# Sheet1.net
KiCad netlist of a schematic drawn in Altium Designer
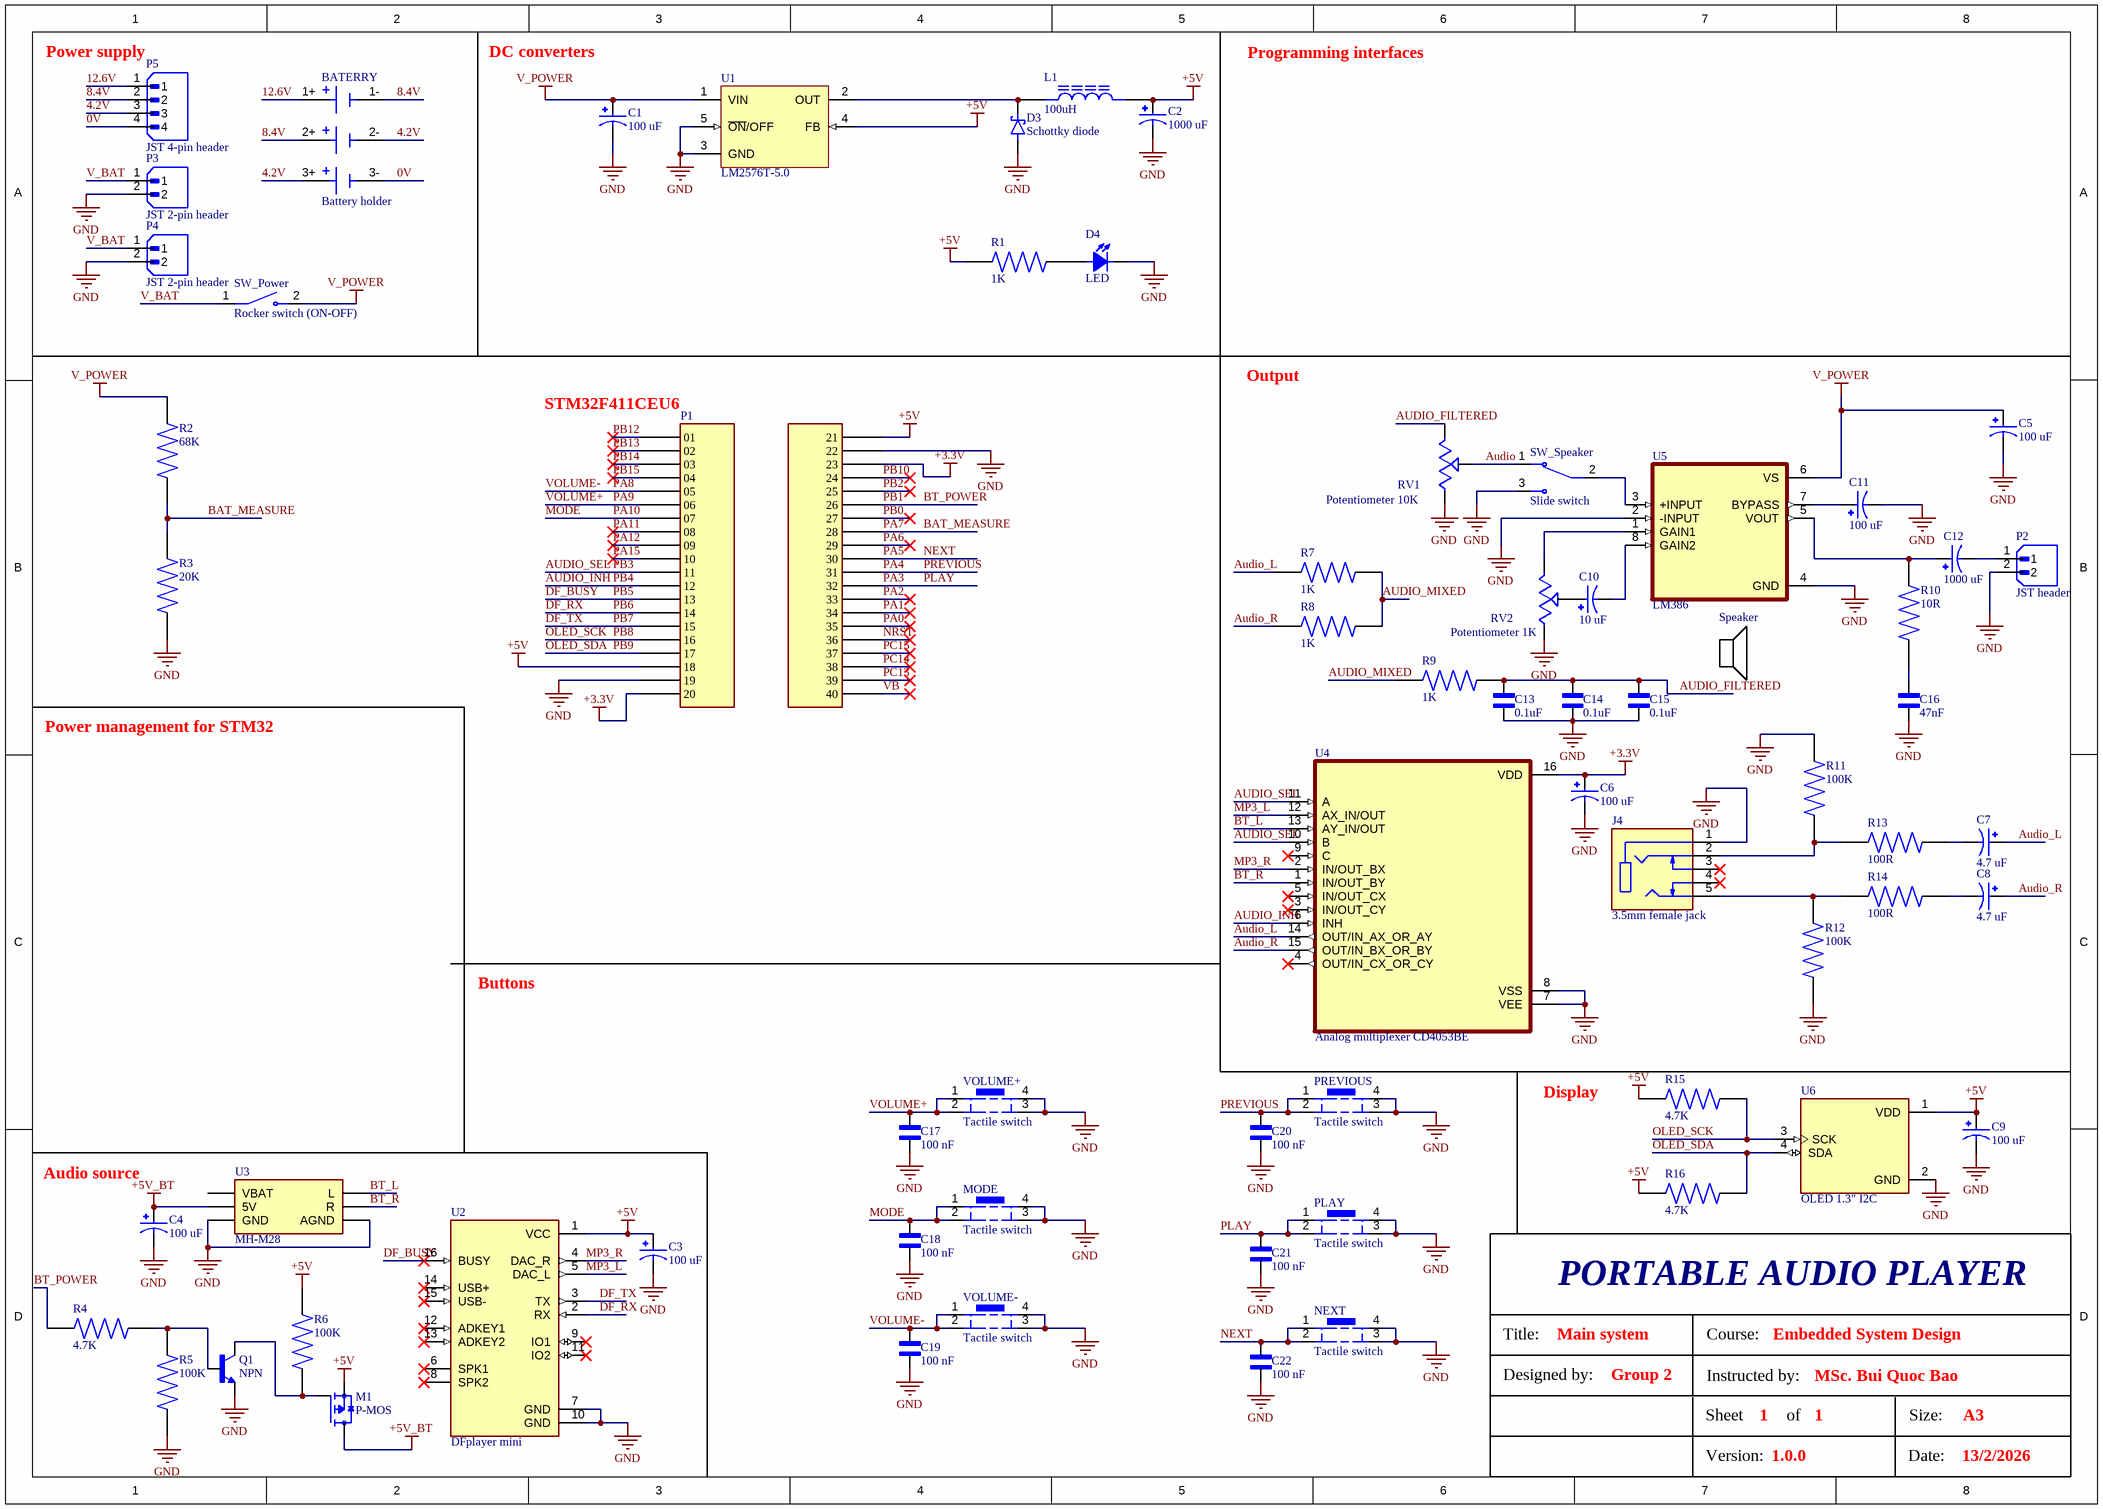
[diagram p0: Sheet1.SchDoc]

(export (version "E")
  (design (tool "Eeschema 10.0.6"))
  (components
    (comp (ref "BATERRY")
      (value "Battery holder")
      (footprint "BAT_BK-18650-PC6")
      (libsource (lib "Schlib1") (part "Battery holder"))
    )
    (comp (ref "C1")
      (value "100 uF")
      (footprint "CAPPRD250W50D630H1120")
      (libsource (lib "Schlib1") (part "100 uF"))
    )
    (comp (ref "C2")
      (value "1000 uF")
      (footprint "CAPPRD500W60D1000H2500")
      (libsource (lib "Schlib1") (part "1000 uF"))
    )
    (comp (ref "C3")
      (value "100 uF")
      (footprint "CAPPRD250W50D630H1120")
      (libsource (lib "Schlib1") (part "100 uF"))
    )
    (comp (ref "C4")
      (value "100 uF")
      (footprint "CAPPRD250W50D630H1120")
      (libsource (lib "Schlib1") (part "100 uF"))
    )
    (comp (ref "C5")
      (value "100 uF")
      (footprint "CAPPRD250W50D630H1120")
      (libsource (lib "Schlib1") (part "100 uF"))
    )
    (comp (ref "C6")
      (value "100 uF")
      (footprint "CAPPRD250W50D630H1120")
      (libsource (lib "Schlib1") (part "100 uF"))
    )
    (comp (ref "C7")
      (value "4.7 uF")
      (footprint "CAPPRD200W50D500H1100")
      (libsource (lib "Schlib1") (part "4.7 uF"))
    )
    (comp (ref "C8")
      (value "4.7 uF")
      (footprint "CAPPRD200W50D500H1100")
      (libsource (lib "Schlib1") (part "4.7 uF"))
    )
    (comp (ref "C9")
      (value "100 uF")
      (footprint "CAPPRD250W50D630H1120")
      (libsource (lib "Schlib1") (part "100 uF"))
    )
    (comp (ref "C10")
      (value "10 uF")
      (footprint "CAPPRD200W50D500H1100")
      (libsource (lib "Schlib1") (part "10 uF"))
    )
    (comp (ref "C11")
      (value "100 uF")
      (footprint "CAPPRD250W50D630H1120")
      (libsource (lib "") (part "100 uF_1"))
    )
    (comp (ref "C12")
      (value "1000 uF")
      (footprint "CAPPRD500W60D1000H2500")
      (libsource (lib "") (part "1000 uF_1"))
    )
    (comp (ref "C13")
      (value "0.1uF")
      (footprint "CAPRR254W54L381T254H466")
      (libsource (lib "Schlib1") (part "0.1uF"))
    )
    (comp (ref "C14")
      (value "0.1uF")
      (footprint "CAPRR254W54L381T254H466")
      (libsource (lib "Schlib1") (part "0.1uF"))
    )
    (comp (ref "C15")
      (value "0.1uF")
      (footprint "CAPRR254W54L381T254H466")
      (libsource (lib "Schlib1") (part "0.1uF"))
    )
    (comp (ref "C16")
      (value "47nF")
      (footprint "CAPRR254W50L508T317H508")
      (libsource (lib "Schlib1") (part "47nF"))
    )
    (comp (ref "C17")
      (value "100 nF")
      (footprint "CAPRR254W54L381T254H466")
      (libsource (lib "Schlib1") (part "100 nF"))
    )
    (comp (ref "C18")
      (value "100 nF")
      (footprint "CAPRR254W54L381T254H466")
      (libsource (lib "Schlib1") (part "100 nF"))
    )
    (comp (ref "C19")
      (value "100 nF")
      (footprint "CAPRR254W54L381T254H466")
      (libsource (lib "Schlib1") (part "100 nF"))
    )
    (comp (ref "C20")
      (value "100 nF")
      (footprint "CAPRR254W54L381T254H466")
      (libsource (lib "Schlib1") (part "100 nF"))
    )
    (comp (ref "C21")
      (value "100 nF")
      (footprint "CAPRR254W54L381T254H466")
      (libsource (lib "Schlib1") (part "100 nF"))
    )
    (comp (ref "C22")
      (value "100 nF")
      (footprint "CAPRR254W54L381T254H466")
      (libsource (lib "Schlib1") (part "100 nF"))
    )
    (comp (ref "D3")
      (value "Schottky diode")
      (footprint "DIOAD1039W78L463D236")
      (libsource (lib "Schlib1") (part "Schottky diode"))
    )
    (comp (ref "D4") (value "LED") (footprint "LED-TH-2.54mm") (libsource (lib "Schlib1") (part "LED")))
    (comp (ref "J4")
      (value "3.5mm female jack")
      (footprint "CLIFF_FC68133")
      (libsource (lib "Schlib1") (part "3.5mm female jack"))
    )
    (comp (ref "L1")
      (value "100uH")
      (footprint "IND_RLB9012-101KL")
      (libsource (lib "Schlib1") (part "100uH"))
    )
    (comp (ref "M1")
      (value "P-MOS")
      (footprint "TO254P1067X483X2286-3")
      (libsource (lib "Schlib1") (part "P-MOS"))
    )
    (comp (ref "MODE")
      (value "Tactile switch")
      (footprint "Tactice-Switch-TH-12x12")
      (libsource (lib "Schlib1") (part "Tactile switch"))
    )
    (comp (ref "NEXT")
      (value "Tactile switch")
      (footprint "Tactice-Switch-TH-12x12")
      (libsource (lib "Schlib1") (part "Tactile switch"))
    )
    (comp (ref "P1")
      (value "2x20 female header for mounting Blackpill board")
      (footprint "Blackpill board mounting headers")
      (libsource (lib "Schlib1") (part "2x20 female header for mounting Blackpill board"))
    )
    (comp (ref "P2")
      (value "JST header")
      (footprint "JST_B2B-XH-A")
      (libsource (lib "Schlib1") (part "JST header"))
    )
    (comp (ref "P3")
      (value "JST 2-pin header")
      (footprint "JST_B2B-XH-A")
      (libsource (lib "Schlib1") (part "JST 2-pin header"))
    )
    (comp (ref "P4")
      (value "JST 2-pin header")
      (footprint "JST_B2B-XH-A")
      (libsource (lib "Schlib1") (part "JST 2-pin header"))
    )
    (comp (ref "P5")
      (value "JST 4-pin header")
      (footprint "JST_B4B-XH-A")
      (libsource (lib "Schlib1") (part "JST 4-pin header"))
    )
    (comp (ref "PLAY")
      (value "Tactile switch")
      (footprint "Tactice-Switch-TH-12x12")
      (libsource (lib "Schlib1") (part "Tactile switch"))
    )
    (comp (ref "PREVIOUS")
      (value "Tactile switch")
      (footprint "Tactice-Switch-TH-12x12")
      (libsource (lib "Schlib1") (part "Tactile switch"))
    )
    (comp (ref "Q1") (value "NPN") (footprint "TO92254P460H750-3") (libsource (lib "Schlib1") (part "NPN")))
    (comp (ref "R1") (value "1K") (footprint "RESAD1100W55L680D260") (libsource (lib "Schlib1") (part "1K")))
    (comp (ref "R2")
      (value "68K")
      (footprint "RESAD1100W55L680D260")
      (libsource (lib "Schlib1") (part "68K"))
    )
    (comp (ref "R3")
      (value "20K")
      (footprint "RESAD1100W55L680D260")
      (libsource (lib "Schlib1") (part "20K"))
    )
    (comp (ref "R4")
      (value "4.7K")
      (footprint "RESAD1100W55L680D260")
      (libsource (lib "Schlib1") (part "4.7K"))
    )
    (comp (ref "R5")
      (value "100K")
      (footprint "RESAD1100W55L680D260")
      (libsource (lib "Schlib1") (part "100K"))
    )
    (comp (ref "R6")
      (value "100K")
      (footprint "RESAD1100W55L680D260")
      (libsource (lib "Schlib1") (part "100K"))
    )
    (comp (ref "R7") (value "1K") (footprint "RESAD1100W55L680D260") (libsource (lib "Schlib1") (part "1K")))
    (comp (ref "R8") (value "1K") (footprint "RESAD1100W55L680D260") (libsource (lib "Schlib1") (part "1K")))
    (comp (ref "R9") (value "1K") (footprint "RESAD1100W55L680D260") (libsource (lib "Schlib1") (part "1K")))
    (comp (ref "R10")
      (value "10R")
      (footprint "RESAD1100W55L680D260")
      (libsource (lib "Schlib1") (part "10R"))
    )
    (comp (ref "R11")
      (value "100K")
      (footprint "RESAD1100W55L680D260")
      (libsource (lib "Schlib1") (part "100K"))
    )
    (comp (ref "R12")
      (value "100K")
      (footprint "RESAD1100W55L680D260")
      (libsource (lib "Schlib1") (part "100K"))
    )
    (comp (ref "R13")
      (value "100R")
      (footprint "RESAD1100W55L680D260")
      (libsource (lib "Schlib1") (part "100R"))
    )
    (comp (ref "R14")
      (value "100R")
      (footprint "RESAD1100W55L680D260")
      (libsource (lib "Schlib1") (part "100R"))
    )
    (comp (ref "R15")
      (value "4.7K")
      (footprint "RESAD1100W55L680D260")
      (libsource (lib "Schlib1") (part "4.7K"))
    )
    (comp (ref "R16")
      (value "4.7K")
      (footprint "RESAD1100W55L680D260")
      (libsource (lib "Schlib1") (part "4.7K"))
    )
    (comp (ref "RV1")
      (value "Potentiometer 10K")
      (footprint "TRIM_WH148-1A-2-18T-L20")
      (libsource (lib "Schlib1") (part "Potentiometer 10K"))
    )
    (comp (ref "RV2")
      (value "Potentiometer 1K")
      (footprint "TRIM_WH148-1A-2-18T-L20")
      (libsource (lib "Schlib1") (part "Potentiometer 1K"))
    )
    (comp (ref "Speaker")
      (value "Speaker")
      (footprint "50mm speaker")
      (libsource (lib "Schlib1") (part "Speaker"))
    )
    (comp (ref "SW_Power")
      (value "Rocker switch (ON-OFF)")
      (footprint "Rocker switch (ON-OFF)")
      (libsource (lib "Schlib1") (part "Rocker switch (ON-OFF)"))
    )
    (comp (ref "SW_Speaker")
      (value "Slide switch")
      (footprint "SW_SLW-1276864-4A-D")
      (libsource (lib "Schlib1") (part "Slide switch"))
    )
    (comp (ref "U1")
      (value "LM2576T-5.0")
      (footprint "KC0005A")
      (description "SIMPLE SWITCHER® 3A Step-Down Voltage Regulator, 5-pin TO-220")
      (fields (field (name "MANUFACTURER") "Texas Instruments"))
      (libsource (lib "Altium Content Vault") (part "PM-REG-LM2575HVT-12"))
    )
    (comp (ref "U2")
      (value "DFplayer mini")
      (footprint "MODULE_DFR0299")
      (libsource (lib "Schlib1") (part "DFplayer mini"))
    )
    (comp (ref "U3") (value "MH-M28") (footprint "MH-M28") (libsource (lib "Schlib1") (part "MH-M28")))
    (comp (ref "U4")
      (value "Analog multiplexer CD4053BE")
      (footprint "DIP_16")
      (libsource (lib "Schlib1") (part "Analog multiplexer CD4053BE"))
    )
    (comp (ref "U5") (value "LM386") (footprint "DIP_8") (libsource (lib "Schlib1") (part "LM386")))
    (comp (ref "U6")
      (value "OLED 1.3\" I2C")
      (footprint "LCD_OLED_128X64_1.3_I2C")
      (libsource (lib "Schlib1") (part "OLED 1.3{dblquote} I2C"))
    )
    (comp (ref "VOLUME+")
      (value "Tactile switch")
      (footprint "Tactice-Switch-TH-12x12")
      (libsource (lib "Schlib1") (part "Tactile switch"))
    )
    (comp (ref "VOLUME-")
      (value "Tactile switch")
      (footprint "Tactice-Switch-TH-12x12")
      (libsource (lib "Schlib1") (part "Tactile switch"))
    )
  )
  (nets
    (net (code "1") (name "+3.3V") (class "Default")
      (node (ref "C6") (pin "P") (pinfunction "P_P") (pintype "passive"))
      (node (ref "P1") (pin "20") (pinfunction "20_20") (pintype "passive"))
      (node (ref "P1") (pin "23") (pinfunction "23_23") (pintype "passive"))
      (node (ref "U4") (pin "16") (pinfunction "VDD_16") (pintype "power_in"))
    )
    (net (code "2") (name "+5V") (class "Default")
      (node (ref "C2") (pin "P") (pinfunction "P_P") (pintype "passive"))
      (node (ref "C3") (pin "P") (pinfunction "P_P") (pintype "passive"))
      (node (ref "C9") (pin "P") (pinfunction "P_P") (pintype "passive"))
      (node (ref "L1") (pin "2") (pinfunction "2_2") (pintype "passive"))
      (node (ref "M1") (pin "3") (pinfunction "S_3") (pintype "passive"))
      (node (ref "P1") (pin "18") (pinfunction "18_18") (pintype "passive"))
      (node (ref "P1") (pin "21") (pinfunction "21_21") (pintype "passive"))
      (node (ref "R1") (pin "1") (pinfunction "1_1") (pintype "passive"))
      (node (ref "R15") (pin "2") (pinfunction "2_2") (pintype "passive"))
      (node (ref "R16") (pin "1") (pinfunction "1_1") (pintype "passive"))
      (node (ref "R6") (pin "2") (pinfunction "2_2") (pintype "passive"))
      (node (ref "U1") (pin "4") (pinfunction "FB_4") (pintype "input"))
      (node (ref "U2") (pin "1") (pinfunction "VCC_1") (pintype "power_in"))
      (node (ref "U6") (pin "1") (pinfunction "VDD_1") (pintype "power_in"))
    )
    (net (code "3") (name "+5V_BT") (class "Default")
      (node (ref "C4") (pin "P") (pinfunction "P_P") (pintype "passive"))
      (node (ref "M1") (pin "2") (pinfunction "D_2") (pintype "passive"))
      (node (ref "U3") (pin "5V") (pinfunction "5V_5V") (pintype "passive"))
    )
    (net (code "4") (name "/0V") (class "Default")
      (node (ref "BATERRY") (pin "3-") (pinfunction "3-_3-") (pintype "passive"))
      (node (ref "P5") (pin "4") (pinfunction "4_4") (pintype "passive"))
    )
    (net (code "5") (name "/4.2V") (class "Default")
      (node (ref "BATERRY") (pin "2-") (pinfunction "2-_2-") (pintype "passive"))
      (node (ref "BATERRY") (pin "3+") (pinfunction "3+_3+") (pintype "passive"))
      (node (ref "P5") (pin "3") (pinfunction "3_3") (pintype "passive"))
    )
    (net (code "6") (name "/8.4V") (class "Default")
      (node (ref "BATERRY") (pin "1-") (pinfunction "1-_1-") (pintype "passive"))
      (node (ref "BATERRY") (pin "2+") (pinfunction "2+_2+") (pintype "passive"))
      (node (ref "P5") (pin "2") (pinfunction "2_2") (pintype "passive"))
    )
    (net (code "7") (name "/12.6V") (class "Default")
      (node (ref "BATERRY") (pin "1+") (pinfunction "1+_1+") (pintype "passive"))
      (node (ref "P5") (pin "1") (pinfunction "1_1") (pintype "passive"))
    )
    (net (code "8") (name "/AUDIO_FILTERED") (class "Default")
      (node (ref "C13") (pin "2") (pinfunction "2_2") (pintype "passive"))
      (node (ref "C14") (pin "2") (pinfunction "2_2") (pintype "passive"))
      (node (ref "C15") (pin "2") (pinfunction "2_2") (pintype "passive"))
      (node (ref "R9") (pin "2") (pinfunction "2_2") (pintype "passive"))
      (node (ref "RV1") (pin "1") (pinfunction "1_1") (pintype "passive"))
    )
    (net (code "9") (name "/AUDIO_INH") (class "Default")
      (node (ref "P1") (pin "12") (pinfunction "12_12") (pintype "passive"))
      (node (ref "U4") (pin "6") (pinfunction "INH_6") (pintype "input"))
    )
    (net (code "10") (name "/AUDIO_MIXED") (class "Default")
      (node (ref "R7") (pin "2") (pinfunction "2_2") (pintype "passive"))
      (node (ref "R8") (pin "2") (pinfunction "2_2") (pintype "passive"))
      (node (ref "R9") (pin "1") (pinfunction "1_1") (pintype "passive"))
    )
    (net (code "11") (name "/AUDIO_SEL") (class "Default")
      (node (ref "P1") (pin "11") (pinfunction "11_11") (pintype "passive"))
      (node (ref "U4") (pin "10") (pinfunction "B_10") (pintype "input"))
      (node (ref "U4") (pin "11") (pinfunction "A_11") (pintype "input"))
    )
    (net (code "12") (name "/Audio") (class "Default")
      (node (ref "RV1") (pin "2") (pinfunction "2_2") (pintype "passive"))
      (node (ref "SW_Speaker") (pin "1") (pinfunction "1_1") (pintype "passive"))
    )
    (net (code "13") (name "/Audio_L") (class "Default")
      (node (ref "C7") (pin "P") (pinfunction "P_P") (pintype "passive"))
      (node (ref "R7") (pin "1") (pinfunction "1_1") (pintype "passive"))
      (node (ref "U4") (pin "14") (pinfunction "OUT/IN_AX_OR_AY_14") (pintype "output"))
    )
    (net (code "14") (name "/Audio_R") (class "Default")
      (node (ref "C8") (pin "P") (pinfunction "P_P") (pintype "passive"))
      (node (ref "R8") (pin "1") (pinfunction "1_1") (pintype "passive"))
      (node (ref "U4") (pin "15") (pinfunction "OUT/IN_BX_OR_BY_15") (pintype "output"))
    )
    (net (code "15") (name "/BAT_MEASURE") (class "Default")
      (node (ref "P1") (pin "28") (pinfunction "28_28") (pintype "passive"))
      (node (ref "R2") (pin "1") (pinfunction "1_1") (pintype "passive"))
      (node (ref "R3") (pin "2") (pinfunction "2_2") (pintype "passive"))
    )
    (net (code "16") (name "/BT_L") (class "Default")
      (node (ref "U3") (pin "L") (pinfunction "L_L") (pintype "passive"))
      (node (ref "U4") (pin "13") (pinfunction "AY_IN/OUT_13") (pintype "input"))
    )
    (net (code "17") (name "/BT_POWER") (class "Default")
      (node (ref "P1") (pin "26") (pinfunction "26_26") (pintype "passive"))
      (node (ref "R4") (pin "1") (pinfunction "1_1") (pintype "passive"))
    )
    (net (code "18") (name "/BT_R") (class "Default")
      (node (ref "U3") (pin "R") (pinfunction "R_R") (pintype "passive"))
      (node (ref "U4") (pin "1") (pinfunction "IN/OUT_BY_1") (pintype "input"))
    )
    (net (code "19") (name "/DF_BUSY") (class "Default")
      (node (ref "P1") (pin "13") (pinfunction "13_13") (pintype "passive"))
      (node (ref "U2") (pin "16") (pinfunction "BUSY_16") (pintype "input"))
    )
    (net (code "20") (name "/DF_RX") (class "Default")
      (node (ref "P1") (pin "14") (pinfunction "14_14") (pintype "passive"))
      (node (ref "U2") (pin "2") (pinfunction "RX_2") (pintype "input"))
    )
    (net (code "21") (name "/DF_TX") (class "Default")
      (node (ref "P1") (pin "15") (pinfunction "15_15") (pintype "passive"))
      (node (ref "U2") (pin "3") (pinfunction "TX_3") (pintype "output"))
    )
    (net (code "22") (name "/MODE") (class "Default")
      (node (ref "C18") (pin "2") (pinfunction "2_2") (pintype "passive"))
      (node (ref "MODE") (pin "1") (pinfunction "1_1") (pintype "passive"))
      (node (ref "MODE") (pin "2") (pinfunction "2_2") (pintype "passive"))
      (node (ref "P1") (pin "7") (pinfunction "07_7") (pintype "passive"))
    )
    (net (code "23") (name "/MP3_L") (class "Default")
      (node (ref "U2") (pin "5") (pinfunction "DAC_L_5") (pintype "output"))
      (node (ref "U4") (pin "12") (pinfunction "AX_IN/OUT_12") (pintype "input"))
    )
    (net (code "24") (name "/MP3_R") (class "Default")
      (node (ref "U2") (pin "4") (pinfunction "DAC_R_4") (pintype "output"))
      (node (ref "U4") (pin "2") (pinfunction "IN/OUT_BX_2") (pintype "input"))
    )
    (net (code "25") (name "/NEXT") (class "Default")
      (node (ref "C22") (pin "2") (pinfunction "2_2") (pintype "passive"))
      (node (ref "NEXT") (pin "1") (pinfunction "1_1") (pintype "passive"))
      (node (ref "NEXT") (pin "2") (pinfunction "2_2") (pintype "passive"))
      (node (ref "P1") (pin "30") (pinfunction "30_30") (pintype "passive"))
    )
    (net (code "26") (name "/NRST") (class "Default")
      (node (ref "P1") (pin "36") (pinfunction "36_36") (pintype "passive+no_connect"))
    )
    (net (code "27") (name "/OLED_SCK") (class "Default")
      (node (ref "P1") (pin "16") (pinfunction "16_16") (pintype "passive"))
      (node (ref "R15") (pin "1") (pinfunction "1_1") (pintype "passive"))
      (node (ref "U6") (pin "3") (pinfunction "SCK_3") (pintype "input"))
    )
    (net (code "28") (name "/OLED_SDA") (class "Default")
      (node (ref "P1") (pin "17") (pinfunction "17_17") (pintype "passive"))
      (node (ref "R16") (pin "2") (pinfunction "2_2") (pintype "passive"))
      (node (ref "U6") (pin "4") (pinfunction "SDA_4") (pintype "bidirectional"))
    )
    (net (code "29") (name "/PA0") (class "Default")
      (node (ref "P1") (pin "35") (pinfunction "35_35") (pintype "passive+no_connect"))
    )
    (net (code "30") (name "/PA1") (class "Default")
      (node (ref "P1") (pin "34") (pinfunction "34_34") (pintype "passive+no_connect"))
    )
    (net (code "31") (name "/PA2") (class "Default")
      (node (ref "P1") (pin "33") (pinfunction "33_33") (pintype "passive+no_connect"))
    )
    (net (code "32") (name "/PA3") (class "Default")
      (node (ref "C21") (pin "2") (pinfunction "2_2") (pintype "passive"))
      (node (ref "P1") (pin "32") (pinfunction "32_32") (pintype "passive"))
      (node (ref "PLAY") (pin "1") (pinfunction "1_1") (pintype "passive"))
      (node (ref "PLAY") (pin "2") (pinfunction "2_2") (pintype "passive"))
    )
    (net (code "33") (name "/PA4") (class "Default")
      (node (ref "C20") (pin "2") (pinfunction "2_2") (pintype "passive"))
      (node (ref "P1") (pin "31") (pinfunction "31_31") (pintype "passive"))
      (node (ref "PREVIOUS") (pin "1") (pinfunction "1_1") (pintype "passive"))
      (node (ref "PREVIOUS") (pin "2") (pinfunction "2_2") (pintype "passive"))
    )
    (net (code "34") (name "/PA6") (class "Default")
      (node (ref "P1") (pin "29") (pinfunction "29_29") (pintype "passive+no_connect"))
    )
    (net (code "35") (name "/PA8") (class "Default")
      (node (ref "C19") (pin "2") (pinfunction "2_2") (pintype "passive"))
      (node (ref "P1") (pin "5") (pinfunction "05_5") (pintype "passive"))
      (node (ref "VOLUME-") (pin "1") (pinfunction "1_1") (pintype "passive"))
      (node (ref "VOLUME-") (pin "2") (pinfunction "2_2") (pintype "passive"))
    )
    (net (code "36") (name "/PA9") (class "Default")
      (node (ref "C17") (pin "2") (pinfunction "2_2") (pintype "passive"))
      (node (ref "P1") (pin "6") (pinfunction "06_6") (pintype "passive"))
      (node (ref "VOLUME+") (pin "1") (pinfunction "1_1") (pintype "passive"))
      (node (ref "VOLUME+") (pin "2") (pinfunction "2_2") (pintype "passive"))
    )
    (net (code "37") (name "/PA11") (class "Default")
      (node (ref "P1") (pin "8") (pinfunction "08_8") (pintype "passive+no_connect"))
    )
    (net (code "38") (name "/PA12") (class "Default")
      (node (ref "P1") (pin "9") (pinfunction "09_9") (pintype "passive+no_connect"))
    )
    (net (code "39") (name "/PA15") (class "Default")
      (node (ref "P1") (pin "10") (pinfunction "10_10") (pintype "passive+no_connect"))
    )
    (net (code "40") (name "/PB0") (class "Default")
      (node (ref "P1") (pin "27") (pinfunction "27_27") (pintype "passive+no_connect"))
    )
    (net (code "41") (name "/PB2") (class "Default")
      (node (ref "P1") (pin "25") (pinfunction "25_25") (pintype "passive+no_connect"))
    )
    (net (code "42") (name "/PB10") (class "Default")
      (node (ref "P1") (pin "24") (pinfunction "24_24") (pintype "passive+no_connect"))
    )
    (net (code "43") (name "/PB12") (class "Default")
      (node (ref "P1") (pin "1") (pinfunction "01_1") (pintype "passive+no_connect"))
    )
    (net (code "44") (name "/PB13") (class "Default")
      (node (ref "P1") (pin "2") (pinfunction "02_2") (pintype "passive+no_connect"))
    )
    (net (code "45") (name "/PB14") (class "Default")
      (node (ref "P1") (pin "3") (pinfunction "03_3") (pintype "passive+no_connect"))
    )
    (net (code "46") (name "/PB15") (class "Default")
      (node (ref "P1") (pin "4") (pinfunction "04_4") (pintype "passive+no_connect"))
    )
    (net (code "47") (name "/PC13") (class "Default")
      (node (ref "P1") (pin "39") (pinfunction "39_39") (pintype "passive+no_connect"))
    )
    (net (code "48") (name "/PC14") (class "Default")
      (node (ref "P1") (pin "38") (pinfunction "38_38") (pintype "passive+no_connect"))
    )
    (net (code "49") (name "/PC15") (class "Default")
      (node (ref "P1") (pin "37") (pinfunction "37_37") (pintype "passive+no_connect"))
    )
    (net (code "50") (name "/VB") (class "Default")
      (node (ref "P1") (pin "40") (pinfunction "40_40") (pintype "passive+no_connect"))
    )
    (net (code "51") (name "/V_BAT") (class "Default")
      (node (ref "P3") (pin "1") (pinfunction "1_1") (pintype "passive"))
      (node (ref "P4") (pin "1") (pinfunction "1_1") (pintype "passive"))
      (node (ref "SW_Power") (pin "1") (pinfunction "1_1") (pintype "passive"))
    )
    (net (code "52") (name "GND") (class "Default")
      (node (ref "C1") (pin "N") (pinfunction "N_N") (pintype "passive"))
      (node (ref "C11") (pin "N") (pinfunction "N_N") (pintype "passive"))
      (node (ref "C13") (pin "1") (pinfunction "1_1") (pintype "passive"))
      (node (ref "C14") (pin "1") (pinfunction "1_1") (pintype "passive"))
      (node (ref "C15") (pin "1") (pinfunction "1_1") (pintype "passive"))
      (node (ref "C16") (pin "1") (pinfunction "1_1") (pintype "passive"))
      (node (ref "C17") (pin "1") (pinfunction "1_1") (pintype "passive"))
      (node (ref "C18") (pin "1") (pinfunction "1_1") (pintype "passive"))
      (node (ref "C19") (pin "1") (pinfunction "1_1") (pintype "passive"))
      (node (ref "C2") (pin "N") (pinfunction "N_N") (pintype "passive"))
      (node (ref "C20") (pin "1") (pinfunction "1_1") (pintype "passive"))
      (node (ref "C21") (pin "1") (pinfunction "1_1") (pintype "passive"))
      (node (ref "C22") (pin "1") (pinfunction "1_1") (pintype "passive"))
      (node (ref "C3") (pin "N") (pinfunction "N_N") (pintype "passive"))
      (node (ref "C4") (pin "N") (pinfunction "N_N") (pintype "passive"))
      (node (ref "C5") (pin "N") (pinfunction "N_N") (pintype "passive"))
      (node (ref "C6") (pin "N") (pinfunction "N_N") (pintype "passive"))
      (node (ref "C9") (pin "N") (pinfunction "N_N") (pintype "passive"))
      (node (ref "D3") (pin "2") (pinfunction "A_2") (pintype "passive"))
      (node (ref "D4") (pin "2") (pinfunction "K_2") (pintype "passive"))
      (node (ref "J4") (pin "1") (pinfunction "1_1") (pintype "passive"))
      (node (ref "MODE") (pin "3") (pinfunction "3_3") (pintype "passive"))
      (node (ref "MODE") (pin "4") (pinfunction "4_4") (pintype "passive"))
      (node (ref "NEXT") (pin "3") (pinfunction "3_3") (pintype "passive"))
      (node (ref "NEXT") (pin "4") (pinfunction "4_4") (pintype "passive"))
      (node (ref "P1") (pin "19") (pinfunction "19_19") (pintype "passive"))
      (node (ref "P1") (pin "22") (pinfunction "22_22") (pintype "passive"))
      (node (ref "P2") (pin "2") (pinfunction "2_2") (pintype "passive"))
      (node (ref "P3") (pin "2") (pinfunction "2_2") (pintype "passive"))
      (node (ref "P4") (pin "2") (pinfunction "2_2") (pintype "passive"))
      (node (ref "PLAY") (pin "3") (pinfunction "3_3") (pintype "passive"))
      (node (ref "PLAY") (pin "4") (pinfunction "4_4") (pintype "passive"))
      (node (ref "PREVIOUS") (pin "3") (pinfunction "3_3") (pintype "passive"))
      (node (ref "PREVIOUS") (pin "4") (pinfunction "4_4") (pintype "passive"))
      (node (ref "Q1") (pin "1") (pinfunction "E_1") (pintype "passive"))
      (node (ref "R11") (pin "2") (pinfunction "2_2") (pintype "passive"))
      (node (ref "R12") (pin "2") (pinfunction "2_2") (pintype "passive"))
      (node (ref "R3") (pin "1") (pinfunction "1_1") (pintype "passive"))
      (node (ref "R5") (pin "1") (pinfunction "1_1") (pintype "passive"))
      (node (ref "RV1") (pin "3") (pinfunction "3_3") (pintype "passive"))
      (node (ref "RV2") (pin "3") (pinfunction "3_3") (pintype "passive"))
      (node (ref "SW_Speaker") (pin "3") (pinfunction "3_3") (pintype "passive"))
      (node (ref "U1") (pin "3") (pinfunction "GND_3") (pintype "power_in"))
      (node (ref "U1") (pin "5") (pinfunction "~{ON}/OFF_5") (pintype "input"))
      (node (ref "U2") (pin "10") (pinfunction "GND_10") (pintype "power_in"))
      (node (ref "U2") (pin "7") (pinfunction "GND_7") (pintype "power_in"))
      (node (ref "U3") (pin "AGND") (pinfunction "AGND_AGND") (pintype "passive"))
      (node (ref "U3") (pin "GND") (pinfunction "GND_GND") (pintype "passive"))
      (node (ref "U4") (pin "7") (pinfunction "VEE_7") (pintype "power_in"))
      (node (ref "U4") (pin "8") (pinfunction "VSS_8") (pintype "power_in"))
      (node (ref "U5") (pin "2") (pinfunction "-INPUT_2") (pintype "input"))
      (node (ref "U5") (pin "4") (pinfunction "GND_4") (pintype "power_in"))
      (node (ref "U6") (pin "2") (pinfunction "GND_2") (pintype "power_in"))
      (node (ref "VOLUME+") (pin "3") (pinfunction "3_3") (pintype "passive"))
      (node (ref "VOLUME+") (pin "4") (pinfunction "4_4") (pintype "passive"))
      (node (ref "VOLUME-") (pin "3") (pinfunction "3_3") (pintype "passive"))
      (node (ref "VOLUME-") (pin "4") (pinfunction "4_4") (pintype "passive"))
    )
    (net (code "53") (name "Net-(C7-PadN)") (class "Default")
      (node (ref "C7") (pin "N") (pinfunction "N_N") (pintype "passive"))
      (node (ref "R13") (pin "2") (pinfunction "2_2") (pintype "passive"))
    )
    (net (code "54") (name "Net-(C8-PadN)") (class "Default")
      (node (ref "C8") (pin "N") (pinfunction "N_N") (pintype "passive"))
      (node (ref "R14") (pin "2") (pinfunction "2_2") (pintype "passive"))
    )
    (net (code "55") (name "Net-(C10-PadP)") (class "Default")
      (node (ref "C10") (pin "P") (pinfunction "P_P") (pintype "passive"))
      (node (ref "RV2") (pin "2") (pinfunction "2_2") (pintype "passive"))
    )
    (net (code "56") (name "Net-(C12-PadN)") (class "Default")
      (node (ref "C12") (pin "N") (pinfunction "N_N") (pintype "passive"))
      (node (ref "P2") (pin "1") (pinfunction "1_1") (pintype "passive"))
    )
    (net (code "57") (name "Net-(C16-Pad2)") (class "Default")
      (node (ref "C16") (pin "2") (pinfunction "2_2") (pintype "passive"))
      (node (ref "R10") (pin "2") (pinfunction "2_2") (pintype "passive"))
    )
    (net (code "58") (name "Net-(D3-K)") (class "Default")
      (node (ref "D3") (pin "1") (pinfunction "K_1") (pintype "passive"))
      (node (ref "L1") (pin "1") (pinfunction "1_1") (pintype "passive"))
      (node (ref "U1") (pin "2") (pinfunction "OUT_2") (pintype "power_in"))
    )
    (net (code "59") (name "Net-(D4-A)") (class "Default")
      (node (ref "D4") (pin "1") (pinfunction "A_1") (pintype "passive"))
      (node (ref "R1") (pin "2") (pinfunction "2_2") (pintype "passive"))
    )
    (net (code "60") (name "Net-(J4-Pad2)") (class "Default")
      (node (ref "J4") (pin "2") (pinfunction "2_2") (pintype "passive"))
      (node (ref "R11") (pin "1") (pinfunction "1_1") (pintype "passive"))
      (node (ref "R13") (pin "1") (pinfunction "1_1") (pintype "passive"))
    )
    (net (code "61") (name "Net-(J4-Pad5)") (class "Default")
      (node (ref "J4") (pin "5") (pinfunction "5_5") (pintype "passive"))
      (node (ref "R12") (pin "1") (pinfunction "1_1") (pintype "passive"))
      (node (ref "R14") (pin "1") (pinfunction "1_1") (pintype "passive"))
    )
    (net (code "62") (name "Net-(M1-G)") (class "Default")
      (node (ref "M1") (pin "1") (pinfunction "G_1") (pintype "passive"))
      (node (ref "Q1") (pin "3") (pinfunction "C_3") (pintype "passive"))
      (node (ref "R6") (pin "1") (pinfunction "1_1") (pintype "passive"))
    )
    (net (code "63") (name "Net-(Q1-B)") (class "Default")
      (node (ref "Q1") (pin "2") (pinfunction "B_2") (pintype "passive"))
      (node (ref "R4") (pin "2") (pinfunction "2_2") (pintype "passive"))
      (node (ref "R5") (pin "2") (pinfunction "2_2") (pintype "passive"))
    )
    (net (code "64") (name "Net-(U5-+INPUT)") (class "Default")
      (node (ref "SW_Speaker") (pin "2") (pinfunction "2_2") (pintype "passive"))
      (node (ref "U5") (pin "3") (pinfunction "+INPUT_3") (pintype "input"))
    )
    (net (code "65") (name "Net-(U5-BYPASS)") (class "Default")
      (node (ref "C11") (pin "P") (pinfunction "P_P") (pintype "passive"))
      (node (ref "U5") (pin "7") (pinfunction "BYPASS_7") (pintype "output"))
    )
    (net (code "66") (name "Net-(U5-GAIN1)") (class "Default")
      (node (ref "RV2") (pin "1") (pinfunction "1_1") (pintype "passive"))
      (node (ref "U5") (pin "1") (pinfunction "GAIN1_1") (pintype "input"))
    )
    (net (code "67") (name "Net-(U5-GAIN2)") (class "Default")
      (node (ref "C10") (pin "N") (pinfunction "N_N") (pintype "passive"))
      (node (ref "U5") (pin "8") (pinfunction "GAIN2_8") (pintype "input"))
    )
    (net (code "68") (name "Net-(U5-VOUT)") (class "Default")
      (node (ref "C12") (pin "P") (pinfunction "P_P") (pintype "passive"))
      (node (ref "R10") (pin "1") (pinfunction "1_1") (pintype "passive"))
      (node (ref "U5") (pin "5") (pinfunction "VOUT_5") (pintype "output"))
    )
    (net (code "69") (name "V_POWER") (class "Default")
      (node (ref "C1") (pin "P") (pinfunction "P_P") (pintype "passive"))
      (node (ref "C5") (pin "P") (pinfunction "P_P") (pintype "passive"))
      (node (ref "R2") (pin "2") (pinfunction "2_2") (pintype "passive"))
      (node (ref "SW_Power") (pin "2") (pinfunction "2_2") (pintype "passive"))
      (node (ref "U1") (pin "1") (pinfunction "VIN_1") (pintype "power_in"))
      (node (ref "U5") (pin "6") (pinfunction "VS_6") (pintype "power_in"))
    )
    (net (code "70") (name "unconnected-(J4-Pad3)") (class "Default")
      (node (ref "J4") (pin "3") (pinfunction "3_3") (pintype "passive+no_connect"))
    )
    (net (code "71") (name "unconnected-(J4-Pad4)") (class "Default")
      (node (ref "J4") (pin "4") (pinfunction "4_4") (pintype "passive+no_connect"))
    )
    (net (code "72") (name "unconnected-(U2-ADKEY1-Pad12)") (class "Default")
      (node (ref "U2") (pin "12") (pinfunction "ADKEY1_12") (pintype "input+no_connect"))
    )
    (net (code "73") (name "unconnected-(U2-ADKEY2-Pad13)") (class "Default")
      (node (ref "U2") (pin "13") (pinfunction "ADKEY2_13") (pintype "input+no_connect"))
    )
    (net (code "74") (name "unconnected-(U2-IO1-Pad9)") (class "Default")
      (node (ref "U2") (pin "9") (pinfunction "IO1_9") (pintype "bidirectional+no_connect"))
    )
    (net (code "75") (name "unconnected-(U2-IO2-Pad11)") (class "Default")
      (node (ref "U2") (pin "11") (pinfunction "IO2_11") (pintype "bidirectional+no_connect"))
    )
    (net (code "76") (name "unconnected-(U2-SPK1-Pad6)") (class "Default")
      (node (ref "U2") (pin "6") (pinfunction "SPK1_6") (pintype "passive+no_connect"))
    )
    (net (code "77") (name "unconnected-(U2-SPK2-Pad8)") (class "Default")
      (node (ref "U2") (pin "8") (pinfunction "SPK2_8") (pintype "passive+no_connect"))
    )
    (net (code "78") (name "unconnected-(U2-USB+-Pad14)") (class "Default")
      (node (ref "U2") (pin "14") (pinfunction "USB+_14") (pintype "input+no_connect"))
    )
    (net (code "79") (name "unconnected-(U2-USB--Pad15)") (class "Default")
      (node (ref "U2") (pin "15") (pinfunction "USB-_15") (pintype "input+no_connect"))
    )
    (net (code "80") (name "unconnected-(U3-PadVBAT)") (class "Default")
      (node (ref "U3") (pin "VBAT") (pinfunction "VBAT_VBAT") (pintype "passive"))
    )
    (net (code "81") (name "unconnected-(U4-C-Pad9)") (class "Default")
      (node (ref "U4") (pin "9") (pinfunction "C_9") (pintype "input+no_connect"))
    )
    (net (code "82") (name "unconnected-(U4-IN{slash}OUT_CX-Pad5)") (class "Default")
      (node (ref "U4") (pin "5") (pinfunction "IN/OUT_CX_5") (pintype "input+no_connect"))
    )
    (net (code "83") (name "unconnected-(U4-IN{slash}OUT_CY-Pad3)") (class "Default")
      (node (ref "U4") (pin "3") (pinfunction "IN/OUT_CY_3") (pintype "input+no_connect"))
    )
    (net (code "84") (name "unconnected-(U4-OUT{slash}IN_CX_OR_CY-Pad4)") (class "Default")
      (node (ref "U4") (pin "4") (pinfunction "OUT/IN_CX_OR_CY_4") (pintype "output+no_connect"))
    )
  )
)
